# AUDIO.net
KiCad netlist of a schematic drawn in Altium Designer
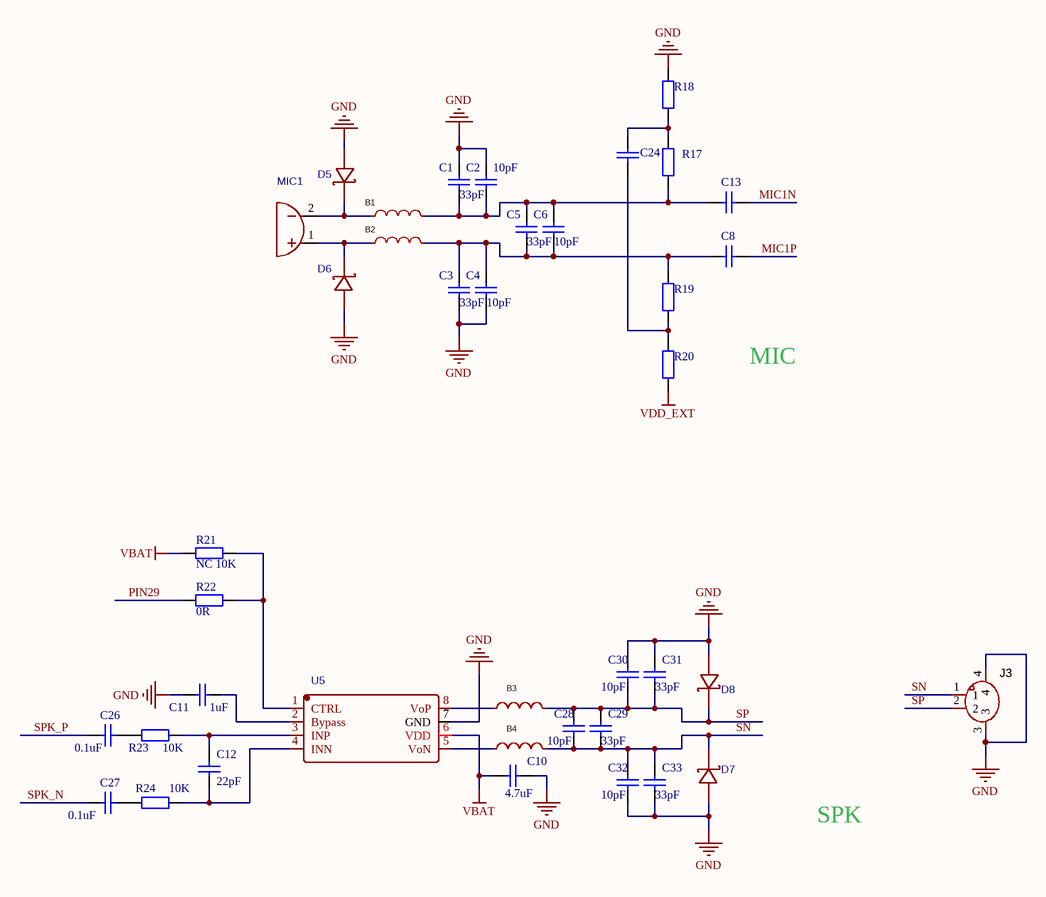
[diagram p0: AUDIO.SchDoc]

(export (version "E")
  (design (tool "Eeschema 10.0.6"))
  (components
    (comp (ref "B1")
      (value "PZ1005U121-1R0TF")
      (footprint "0402R")
      (description "磁珠")
      (fields (field (name "MANUFACTURER") "Sunlord(顺络)") (field (name "TOLERANCE") "±25%"))
      (libsource (lib "altium-import") (part "root_0_PZ1005U121-1R0TF_"))
    )
    (comp (ref "B2")
      (value "PZ1005U121-1R0TF")
      (footprint "0402R")
      (description "磁珠")
      (fields (field (name "MANUFACTURER") "Sunlord(顺络)") (field (name "TOLERANCE") "±25%"))
      (libsource (lib "altium-import") (part "root_0_PZ1005U121-1R0TF_"))
    )
    (comp (ref "B3")
      (value "PZ1005U121-1R0TF")
      (footprint "0402R")
      (description "磁珠")
      (fields (field (name "MANUFACTURER") "Sunlord(顺络)") (field (name "TOLERANCE") "±25%"))
      (libsource (lib "altium-import") (part "root_0_PZ1005U121-1R0TF_"))
    )
    (comp (ref "B4")
      (value "PZ1005U121-1R0TF")
      (footprint "0402R")
      (description "磁珠")
      (fields (field (name "MANUFACTURER") "Sunlord(顺络)") (field (name "TOLERANCE") "±25%"))
      (libsource (lib "altium-import") (part "root_0_PZ1005U121-1R0TF_"))
    )
    (comp (ref "C1")
      (value "33pF")
      (footprint "0402C")
      (description "Capacitor")
      (fields (field (name "Comment") "22pF") (field (name "PUBLISHER") "Altium Limited"))
      (libsource (lib "Miscellaneous Devices") (part "Cap"))
    )
    (comp (ref "C2")
      (value "10pF")
      (footprint "0402C")
      (description "Capacitor")
      (fields (field (name "PUBLISHER") "Altium Limited"))
      (libsource (lib "Miscellaneous Devices") (part "Cap"))
    )
    (comp (ref "C3")
      (value "33pF")
      (footprint "0402C")
      (description "Capacitor")
      (fields (field (name "Comment") "22pF") (field (name "PUBLISHER") "Altium Limited"))
      (libsource (lib "Miscellaneous Devices") (part "Cap"))
    )
    (comp (ref "C4")
      (value "10pF")
      (footprint "0402C")
      (description "Capacitor")
      (fields (field (name "PUBLISHER") "Altium Limited"))
      (libsource (lib "Miscellaneous Devices") (part "Cap"))
    )
    (comp (ref "C5")
      (value "33pF")
      (footprint "0402C")
      (description "Capacitor")
      (fields (field (name "Comment") "22pF") (field (name "PUBLISHER") "Altium Limited"))
      (libsource (lib "Miscellaneous Devices") (part "Cap"))
    )
    (comp (ref "C6")
      (value "10pF")
      (footprint "0402C")
      (description "Capacitor")
      (fields (field (name "PUBLISHER") "Altium Limited"))
      (libsource (lib "Miscellaneous Devices") (part "Cap"))
    )
    (comp (ref "C8")
      (value "0.1uF")
      (footprint "0402C")
      (description "Capacitor")
      (fields (field (name "PUBLISHER") "Altium Limited"))
      (libsource (lib "Miscellaneous Devices") (part "Cap"))
    )
    (comp (ref "C10")
      (value "4.7uF")
      (footprint "0402C")
      (description "Capacitor")
      (fields (field (name "PUBLISHER") "Altium Limited"))
      (libsource (lib "Miscellaneous Devices") (part "Cap"))
    )
    (comp (ref "C11")
      (value "1uF")
      (footprint "0402C")
      (description "Capacitor")
      (fields (field (name "PUBLISHER") "Altium Limited"))
      (libsource (lib "Miscellaneous Devices") (part "Cap"))
    )
    (comp (ref "C12")
      (value "22pF")
      (footprint "0402C")
      (description "Capacitor")
      (fields (field (name "PUBLISHER") "Altium Limited"))
      (libsource (lib "Miscellaneous Devices") (part "Cap"))
    )
    (comp (ref "C13")
      (value "0.1uF")
      (footprint "0402C")
      (description "Capacitor")
      (fields (field (name "PUBLISHER") "Altium Limited"))
      (libsource (lib "Miscellaneous Devices") (part "Cap"))
    )
    (comp (ref "C24")
      (value "10uF")
      (footprint "0402C")
      (description "Capacitor")
      (fields (field (name "PUBLISHER") "Altium Limited"))
      (libsource (lib "Miscellaneous Devices") (part "Cap"))
    )
    (comp (ref "C26")
      (value "0.1uF")
      (footprint "0402C")
      (description "Capacitor")
      (fields (field (name "PUBLISHER") "Altium Limited"))
      (libsource (lib "Miscellaneous Devices") (part "Cap"))
    )
    (comp (ref "C27")
      (value "0.1uF")
      (footprint "0402C")
      (description "Capacitor")
      (fields (field (name "PUBLISHER") "Altium Limited"))
      (libsource (lib "Miscellaneous Devices") (part "Cap"))
    )
    (comp (ref "C28")
      (value "10pF")
      (footprint "0402C")
      (description "Capacitor")
      (fields (field (name "PUBLISHER") "Altium Limited"))
      (libsource (lib "Miscellaneous Devices") (part "Cap"))
    )
    (comp (ref "C29")
      (value "33pF")
      (footprint "0402C")
      (description "Capacitor")
      (fields (field (name "Comment") "22pF") (field (name "PUBLISHER") "Altium Limited"))
      (libsource (lib "Miscellaneous Devices") (part "Cap"))
    )
    (comp (ref "C30")
      (value "10pF")
      (footprint "0402C")
      (description "Capacitor")
      (fields (field (name "PUBLISHER") "Altium Limited"))
      (libsource (lib "Miscellaneous Devices") (part "Cap"))
    )
    (comp (ref "C31")
      (value "33pF")
      (footprint "0402C")
      (description "Capacitor")
      (fields (field (name "Comment") "22pF") (field (name "PUBLISHER") "Altium Limited"))
      (libsource (lib "Miscellaneous Devices") (part "Cap"))
    )
    (comp (ref "C32")
      (value "10pF")
      (footprint "0402C")
      (description "Capacitor")
      (fields (field (name "PUBLISHER") "Altium Limited"))
      (libsource (lib "Miscellaneous Devices") (part "Cap"))
    )
    (comp (ref "C33")
      (value "33pF")
      (footprint "0402C")
      (description "Capacitor")
      (fields (field (name "Comment") "22pF") (field (name "PUBLISHER") "Altium Limited"))
      (libsource (lib "Miscellaneous Devices") (part "Cap"))
    )
    (comp (ref "D5")
      (value "LESD8LL5.0T5G")
      (footprint "SOD-882_L1.0-W0.6-RD")
      (description "ESD")
      (fields (field (name "BOM_SUPPLIER PART") "C172423") (field (name "CONTRIBUTOR") "LCSC"))
      (libsource (lib "altium-import") (part "root_1_LESD8LL5.0T5G_"))
    )
    (comp (ref "D6")
      (value "LESD8LL5.0T5G")
      (footprint "SOD-882_L1.0-W0.6-RD")
      (description "ESD")
      (fields (field (name "BOM_SUPPLIER PART") "C172423") (field (name "CONTRIBUTOR") "LCSC"))
      (libsource (lib "altium-import") (part "root_3_LESD8LL5.0T5G_"))
    )
    (comp (ref "D7")
      (value "LESD8LL5.0T5G")
      (footprint "SOD-882_L1.0-W0.6-RD")
      (description "ESD")
      (fields (field (name "BOM_SUPPLIER PART") "C172423") (field (name "CONTRIBUTOR") "LCSC"))
      (libsource (lib "altium-import") (part "root_3_LESD8LL5.0T5G_"))
    )
    (comp (ref "D8")
      (value "LESD8LL5.0T5G")
      (footprint "SOD-882_L1.0-W0.6-RD")
      (description "ESD")
      (fields (field (name "BOM_SUPPLIER PART") "C172423") (field (name "CONTRIBUTOR") "LCSC"))
      (libsource (lib "altium-import") (part "root_1_LESD8LL5.0T5G_"))
    )
    (comp (ref "J3")
      (value "WAFER-MX1.25-2PWB")
      (footprint "CONN-SMD_2P-P1.25_XUNPU_WAFER-MX1.25-2PWB")
      (description "WAFER")
      (fields (field (name "MANUFACTURER") "XUNPU(讯普)"))
      (libsource (lib "altium-import") (part "root_0_WAFER-MX1.25-2PWB_"))
    )
    (comp (ref "MIC1")
      (value "B4013AM423-092")
      (footprint "MIC-SMD_BD4.0_B4013AM423-008")
      (description "MIC")
      (fields (field (name "BOM_SUPPLIER PART") "C5160218") (field (name "CONTRIBUTOR") "LCSC"))
      (libsource (lib "altium-import") (part "root_1_GMI6050P-66DB_"))
    )
    (comp (ref "R17")
      (value "1.5K")
      (footprint "0402R")
      (description "Resistor")
      (fields (field (name "PUBLISHER") "Altium Limited"))
      (libsource (lib "") (part "Res2_1"))
    )
    (comp (ref "R18")
      (value "1K")
      (footprint "0402R")
      (description "Resistor")
      (fields (field (name "PUBLISHER") "Altium Limited"))
      (libsource (lib "") (part "Res2_1"))
    )
    (comp (ref "R19")
      (value "1.5K")
      (footprint "0402R")
      (description "Resistor")
      (fields (field (name "PUBLISHER") "Altium Limited"))
      (libsource (lib "") (part "Res2_1"))
    )
    (comp (ref "R20")
      (value "1K")
      (footprint "0402R")
      (description "Resistor")
      (fields (field (name "PUBLISHER") "Altium Limited"))
      (libsource (lib "") (part "Res2_1"))
    )
    (comp (ref "R21")
      (value "NC 10K")
      (footprint "0402R")
      (description "Resistor")
      (fields (field (name "PUBLISHER") "Altium Limited"))
      (libsource (lib "") (part "Res2_2"))
    )
    (comp (ref "R22")
      (value "0R")
      (footprint "0402R")
      (description "Resistor")
      (fields (field (name "PUBLISHER") "Altium Limited"))
      (libsource (lib "Miscellaneous Devices") (part "Res2"))
    )
    (comp (ref "R23")
      (value "10K")
      (footprint "0402R")
      (description "Resistor")
      (fields (field (name "PUBLISHER") "Altium Limited"))
      (libsource (lib "Miscellaneous Devices") (part "Res2"))
    )
    (comp (ref "R24")
      (value "10K")
      (footprint "0402R")
      (description "Resistor")
      (fields (field (name "PUBLISHER") "Altium Limited"))
      (libsource (lib "Miscellaneous Devices") (part "Res2"))
    )
    (comp (ref "U5")
      (value "NS4150C")
      (footprint "SOIC-8_150mil_NS4150C")
      (description "Amplifier")
      (fields
        (field (name "BOM_SUPPLIER PART") "C219017")
        (field (name "BOM_MANUFACTURER PART") "NS4160")
        (field (name "CONTRIBUTOR") "LCSC")
      )
      (libsource (lib "altium-import") (part "root_0_NS4160_"))
    )
  )
  (nets
    (net (code "1") (name "/MIC1N") (class "Default")
      (node (ref "C13") (pin "1") (pinfunction "1_1") (pintype "passive"))
    )
    (net (code "2") (name "/MIC1P") (class "Default")
      (node (ref "C8") (pin "1") (pinfunction "1_1") (pintype "passive"))
    )
    (net (code "3") (name "/PIN29") (class "Default")
      (node (ref "R22") (pin "1") (pinfunction "1_1") (pintype "passive"))
    )
    (net (code "4") (name "/SN") (class "Default")
      (node (ref "B4") (pin "2") (pinfunction "2_2") (pintype "passive"))
      (node (ref "C28") (pin "1") (pinfunction "1_1") (pintype "passive"))
      (node (ref "C29") (pin "1") (pinfunction "1_1") (pintype "passive"))
      (node (ref "C32") (pin "2") (pinfunction "2_2") (pintype "passive"))
      (node (ref "C33") (pin "2") (pinfunction "2_2") (pintype "passive"))
      (node (ref "D7") (pin "1") (pinfunction "C_1") (pintype "passive"))
      (node (ref "J3") (pin "1") (pinfunction "1_1") (pintype "passive"))
    )
    (net (code "5") (name "/SP") (class "Default")
      (node (ref "B3") (pin "2") (pinfunction "2_2") (pintype "passive"))
      (node (ref "C28") (pin "2") (pinfunction "2_2") (pintype "passive"))
      (node (ref "C29") (pin "2") (pinfunction "2_2") (pintype "passive"))
      (node (ref "C30") (pin "1") (pinfunction "1_1") (pintype "passive"))
      (node (ref "C31") (pin "1") (pinfunction "1_1") (pintype "passive"))
      (node (ref "D8") (pin "1") (pinfunction "C_1") (pintype "passive"))
      (node (ref "J3") (pin "2") (pinfunction "2_2") (pintype "passive"))
    )
    (net (code "6") (name "/SPK_N") (class "Default")
      (node (ref "C27") (pin "1") (pinfunction "1_1") (pintype "passive"))
    )
    (net (code "7") (name "/SPK_P") (class "Default")
      (node (ref "C26") (pin "1") (pinfunction "1_1") (pintype "passive"))
    )
    (net (code "8") (name "GND") (class "Default")
      (node (ref "C1") (pin "2") (pinfunction "2_2") (pintype "passive"))
      (node (ref "C10") (pin "2") (pinfunction "2_2") (pintype "passive"))
      (node (ref "C11") (pin "1") (pinfunction "1_1") (pintype "passive"))
      (node (ref "C2") (pin "2") (pinfunction "2_2") (pintype "passive"))
      (node (ref "C3") (pin "1") (pinfunction "1_1") (pintype "passive"))
      (node (ref "C30") (pin "2") (pinfunction "2_2") (pintype "passive"))
      (node (ref "C31") (pin "2") (pinfunction "2_2") (pintype "passive"))
      (node (ref "C32") (pin "1") (pinfunction "1_1") (pintype "passive"))
      (node (ref "C33") (pin "1") (pinfunction "1_1") (pintype "passive"))
      (node (ref "C4") (pin "1") (pinfunction "1_1") (pintype "passive"))
      (node (ref "D5") (pin "2") (pinfunction "A_2") (pintype "passive"))
      (node (ref "D6") (pin "2") (pinfunction "A_2") (pintype "passive"))
      (node (ref "D7") (pin "2") (pinfunction "A_2") (pintype "passive"))
      (node (ref "D8") (pin "2") (pinfunction "A_2") (pintype "passive"))
      (node (ref "J3") (pin "3") (pinfunction "3_3") (pintype "passive"))
      (node (ref "J3") (pin "4") (pinfunction "4_4") (pintype "passive"))
      (node (ref "R18") (pin "2") (pinfunction "2_2") (pintype "passive"))
      (node (ref "U5") (pin "7") (pinfunction "GND_7") (pintype "passive"))
    )
    (net (code "9") (name "Net-(B1-Pad2)") (class "Default")
      (node (ref "B1") (pin "2") (pinfunction "2_2") (pintype "passive"))
      (node (ref "C1") (pin "1") (pinfunction "1_1") (pintype "passive"))
      (node (ref "C13") (pin "2") (pinfunction "2_2") (pintype "passive"))
      (node (ref "C2") (pin "1") (pinfunction "1_1") (pintype "passive"))
      (node (ref "C5") (pin "2") (pinfunction "2_2") (pintype "passive"))
      (node (ref "C6") (pin "2") (pinfunction "2_2") (pintype "passive"))
      (node (ref "R17") (pin "1") (pinfunction "1_1") (pintype "passive"))
    )
    (net (code "10") (name "Net-(B2-Pad2)") (class "Default")
      (node (ref "B2") (pin "2") (pinfunction "2_2") (pintype "passive"))
      (node (ref "C3") (pin "2") (pinfunction "2_2") (pintype "passive"))
      (node (ref "C4") (pin "2") (pinfunction "2_2") (pintype "passive"))
      (node (ref "C5") (pin "1") (pinfunction "1_1") (pintype "passive"))
      (node (ref "C6") (pin "1") (pinfunction "1_1") (pintype "passive"))
      (node (ref "C8") (pin "2") (pinfunction "2_2") (pintype "passive"))
      (node (ref "R19") (pin "2") (pinfunction "2_2") (pintype "passive"))
    )
    (net (code "11") (name "Net-(C24-Pad1)") (class "Default")
      (node (ref "C24") (pin "1") (pinfunction "1_1") (pintype "passive"))
      (node (ref "R17") (pin "2") (pinfunction "2_2") (pintype "passive"))
      (node (ref "R18") (pin "1") (pinfunction "1_1") (pintype "passive"))
    )
    (net (code "12") (name "Net-(C24-Pad2)") (class "Default")
      (node (ref "C24") (pin "2") (pinfunction "2_2") (pintype "passive"))
      (node (ref "R19") (pin "1") (pinfunction "1_1") (pintype "passive"))
      (node (ref "R20") (pin "2") (pinfunction "2_2") (pintype "passive"))
    )
    (net (code "13") (name "Net-(C26-Pad2)") (class "Default")
      (node (ref "C26") (pin "2") (pinfunction "2_2") (pintype "passive"))
      (node (ref "R23") (pin "1") (pinfunction "1_1") (pintype "passive"))
    )
    (net (code "14") (name "Net-(C27-Pad2)") (class "Default")
      (node (ref "C27") (pin "2") (pinfunction "2_2") (pintype "passive"))
      (node (ref "R24") (pin "1") (pinfunction "1_1") (pintype "passive"))
    )
    (net (code "15") (name "Net-(D5-C)") (class "Default")
      (node (ref "B1") (pin "1") (pinfunction "1_1") (pintype "passive"))
      (node (ref "D5") (pin "1") (pinfunction "C_1") (pintype "passive"))
      (node (ref "MIC1") (pin "2") (pinfunction "2_2") (pintype "passive"))
    )
    (net (code "16") (name "Net-(D6-C)") (class "Default")
      (node (ref "B2") (pin "1") (pinfunction "1_1") (pintype "passive"))
      (node (ref "D6") (pin "1") (pinfunction "C_1") (pintype "passive"))
      (node (ref "MIC1") (pin "1") (pinfunction "1_1") (pintype "passive"))
    )
    (net (code "17") (name "Net-(U5-Bypass)") (class "Default")
      (node (ref "C11") (pin "2") (pinfunction "2_2") (pintype "passive"))
      (node (ref "U5") (pin "2") (pinfunction "Bypass_2") (pintype "passive"))
    )
    (net (code "18") (name "Net-(U5-CTRL)") (class "Default")
      (node (ref "R21") (pin "1") (pinfunction "1_1") (pintype "passive"))
      (node (ref "R22") (pin "2") (pinfunction "2_2") (pintype "passive"))
      (node (ref "U5") (pin "1") (pinfunction "CTRL_1") (pintype "passive"))
    )
    (net (code "19") (name "Net-(U5-INN)") (class "Default")
      (node (ref "C12") (pin "2") (pinfunction "2_2") (pintype "passive"))
      (node (ref "R24") (pin "2") (pinfunction "2_2") (pintype "passive"))
      (node (ref "U5") (pin "4") (pinfunction "INN_4") (pintype "passive"))
    )
    (net (code "20") (name "Net-(U5-INP)") (class "Default")
      (node (ref "C12") (pin "1") (pinfunction "1_1") (pintype "passive"))
      (node (ref "R23") (pin "2") (pinfunction "2_2") (pintype "passive"))
      (node (ref "U5") (pin "3") (pinfunction "INP_3") (pintype "passive"))
    )
    (net (code "21") (name "Net-(U5-VoN)") (class "Default")
      (node (ref "B4") (pin "1") (pinfunction "1_1") (pintype "passive"))
      (node (ref "U5") (pin "5") (pinfunction "VoN_5") (pintype "passive"))
    )
    (net (code "22") (name "Net-(U5-VoP)") (class "Default")
      (node (ref "B3") (pin "1") (pinfunction "1_1") (pintype "passive"))
      (node (ref "U5") (pin "8") (pinfunction "VoP_8") (pintype "passive"))
    )
    (net (code "23") (name "VBAT") (class "Default")
      (node (ref "C10") (pin "1") (pinfunction "1_1") (pintype "passive"))
      (node (ref "R21") (pin "2") (pinfunction "2_2") (pintype "passive"))
      (node (ref "U5") (pin "6") (pinfunction "VDD_6") (pintype "passive"))
    )
    (net (code "24") (name "VDD_EXT") (class "Default")
      (node (ref "R20") (pin "1") (pinfunction "1_1") (pintype "passive"))
    )
  )
)
